# node24-power.net
KiCad netlist of a schematic drawn in Altium Designer
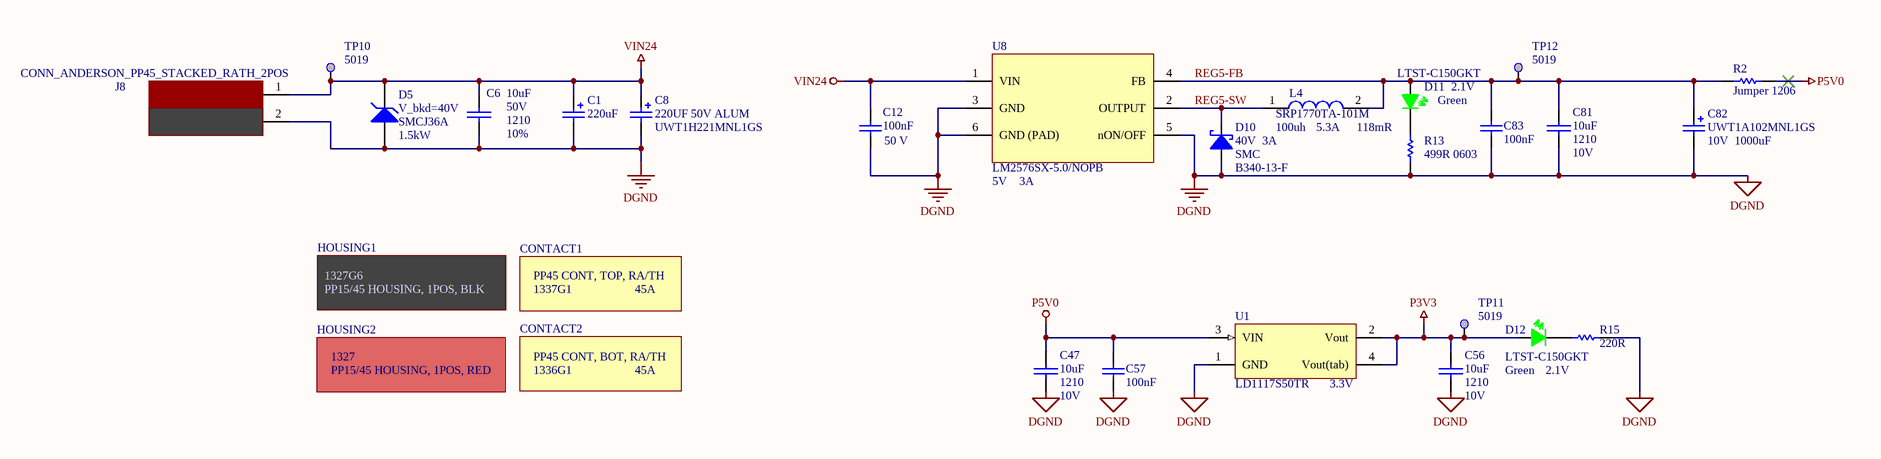
[diagram p0: node24-power.SchDoc]

(export (version "E")
  (design (tool "Eeschema 10.0.6"))
  (components
    (comp (ref "C1")
      (value "220UF ALUM 10MM")
      (footprint "CAPAE_D10_BH10MM3")
      (description "CAP ALUM 220UF 20% 50V SMD")
      (fields
        (field (name "MANUFACTURER") "Nichicon")
        (field (name "CAPACITANCE") "220uF")
        (field (name "TOLERANCE") "20%")
      )
      (libsource (lib "node") (part "CAP_ALUM_220UF_10MM_UWT1H221MNL1GS"))
    )
    (comp (ref "C6")
      (value "CAP_CER_10UF_50V_1210_GRJ32ER71H106KE11L")
      (footprint "CAP1210")
      (description "10µF 50V Ceramic Capacitor X7R 1210 (3225 Metric) 0.126\" L x 0.098\" W (3.20mm x 2.50mm)")
      (fields
        (field (name "MANUFACTURER") "Murata")
        (field (name "MANUFACTURER PART NUMBER") "GRJ32ER71H106KE11L")
        (field (name "TOLERANCE") "10%")
        (field (name "VOLTAGE RATING") "50V")
        (field (name "CAPACITANCE") "10uF")
        (field (name "CASE/PACKAGE") "1210")
      )
      (libsource (lib "node") (part "CAP_CER_10UF_50V_1210_GRJ32ER71H106KE11L"))
    )
    (comp (ref "C8")
      (value "220UF 50V ALUM")
      (footprint "CAPAE_D10_BH10MM3")
      (description "CAP ALUM 220UF 20% 50V SMD")
      (fields
        (field (name "MANUFACTURER") "Nichicon")
        (field (name "TOLERANCE") "20%")
        (field (name "MANUFACTURER PART NUMBER") "UWT1H221MNL1GS")
      )
      (libsource (lib "node") (part "CAP_ALUM_220UF_10MM_UWT1H221MNL1GS"))
    )
    (comp (ref "C12")
      (value "100nF")
      (footprint "CAPC0603(1608)100_L")
      (description "CAP 100nF 50V ±20% 0603 (1608 Metric) Thickness 1mm SMD")
      (fields (field (name "TOLERANCE") "Â±20%") (field (name "RATED VOLTAGE") "50 V"))
      (libsource (lib "Altium Content Vault") (part "CAP"))
    )
    (comp (ref "C47")
      (value "CAP_CER_10UF_1210_CL32B106KPINNNE")
      (footprint "1210C")
      (description "Cap Ceramic 10uF 10V X7R 10% SMD 1210 125C Embossed T/R")
      (fields
        (field (name "MANUFACTURER") "Samsung")
        (field (name "MANUFACTURER PART NUMBER") "CL32B106KPINNNE")
        (field (name "CAPACITANCE") "10uF")
        (field (name "CASE/PACKAGE") "1210")
        (field (name "VOLTAGE RATING") "10V")
      )
      (libsource (lib "node") (part "CAP_CER_10UF_1210_CL32B106KPINNNE"))
    )
    (comp (ref "C56")
      (value "CAP_CER_10UF_1210_CL32B106KPINNNE")
      (footprint "1210C")
      (description "Cap Ceramic 10uF 10V X7R 10% SMD 1210 125C Embossed T/R")
      (fields
        (field (name "MANUFACTURER") "Samsung")
        (field (name "MANUFACTURER PART NUMBER") "CL32B106KPINNNE")
        (field (name "CAPACITANCE") "10uF")
        (field (name "CASE/PACKAGE") "1210")
        (field (name "VOLTAGE RATING") "10V")
      )
      (libsource (lib "node") (part "CAP_CER_10UF_1210_CL32B106KPINNNE"))
    )
    (comp (ref "C57")
      (value "100nF")
      (footprint "CAPC0603(1608)100_L")
      (description "CAP 100nF 50V ±20% 0603 (1608 Metric) Thickness 1mm SMD")
      (fields (field (name "TOLERANCE") "Â±20%"))
      (libsource (lib "Altium Content Vault") (part "CAP"))
    )
    (comp (ref "C81")
      (value "CAP_CER_10UF_1210_CL32B106KPINNNE")
      (footprint "1210C")
      (description "Cap Ceramic 10uF 10V X7R 10% SMD 1210 125C Embossed T/R")
      (fields
        (field (name "MANUFACTURER") "Samsung")
        (field (name "MANUFACTURER PART NUMBER") "CL32B106KPINNNE")
        (field (name "CAPACITANCE") "10uF")
        (field (name "CASE/PACKAGE") "1210")
        (field (name "VOLTAGE RATING") "10V")
      )
      (libsource (lib "node") (part "CAP_CER_10UF_1210_CL32B106KPINNNE"))
    )
    (comp (ref "C82")
      (value "CAP_ALUM_10V_1000UF_10MM_UWT1A102MNL1GS")
      (footprint "CAPAE_D10_BH10MM3")
      (description "CAP ALUM 1000UF 20% 10V SMD")
      (fields
        (field (name "MANUFACTURER") "Nichicon")
        (field (name "TOLERANCE") "20%")
        (field (name "MANUFACTURER PART NUMBER") "UWT1A102MNL1GS")
        (field (name "VOLTAGE") "10V")
        (field (name "CAPACITANCE") "1000uF")
      )
      (libsource (lib "node") (part "CAP_ALUM_10V_1000UF_10MM_UWT1A102MNL1GS"))
    )
    (comp (ref "C83")
      (value "100nF")
      (footprint "CAPC0603(1608)100_L")
      (description "CAP 100nF 50V ±20% 0603 (1608 Metric) Thickness 1mm SMD")
      (fields (field (name "TOLERANCE") "Â±20%"))
      (libsource (lib "Altium Content Vault") (part "CAP"))
    )
    (comp (ref "CONTACT1")
      (value "CONN_ANDERSON_CONTACT_PP45_RATH_BOTTOM_1337G1")
      (description "Heavy Duty Power Connectors PCB45 HORIZ (TOP) RA LP CONT.")
      (fields
        (field (name "MANUFACTURER") "Anderson Power")
        (field (name "CURRENT RATING") "45A")
        (field (name "MANUFACTURER PART NUMBER") "1337G1")
        (field (name "PARAMETER 1") "PP45 CONT, TOP, RA/TH")
      )
      (libsource (lib "node") (part "CONN_ANDERSON_CONTACT_PP45_RATH_BOTTOM_1337G1"))
    )
    (comp (ref "CONTACT2")
      (value "CONN_ANDERSON_CONTACT_PP45_RATH_TOP_1336G1")
      (description "Heavy Duty Power Connectors PCB45 HORIZ. (BOT) RA LP CONT.")
      (fields
        (field (name "MANUFACTURER") "Anderson Power")
        (field (name "PARAMETER 1") "PP45 CONT, BOT, RA/TH")
        (field (name "CURRENT RATING") "45A")
        (field (name "MANUFACTURER PART NUMBER") "1336G1")
      )
      (libsource (lib "node") (part "CONN_ANDERSON_CONTACT_PP45_RATH_TOP_1336G1"))
    )
    (comp (ref "D5")
      (value "TVS_36V_1500W_SMC_SMCJ36A")
      (footprint "DIODE_SMC")
      (description "TVS DIODE 36VWM 58.1VC SMC")
      (fields
        (field (name "MANUFACTURER") "Littelfuse")
        (field (name "POWER DISSIPATION") "1.5kW")
        (field (name "MANUFACTURER PART NUMBER") "SMCJ36A")
        (field (name "BREAKDOWN VOLTAGE") "V_bkd=40V")
      )
      (libsource (lib "node") (part "TVS_36V_1500W_SMC_SMCJ36A"))
    )
    (comp (ref "D10")
      (value "DIODE_SCHOTTKY_40V_3A_SMC_DIO_B340-13-F")
      (footprint "DIODE_SMC")
      (description "DIODE SCHOTTKY 40V 3A SMC")
      (fields
        (field (name "MANUFACTURER") "Diodes")
        (field (name "VOLTAGE") "40V")
        (field (name "MANUFACTURER PART NUMBER") "B340-13-F")
        (field (name "CASE/PACKAGE") "SMC")
        (field (name "MAX REVERSE VOLTAGE (DC)") "40V")
        (field (name "CURRENT") "3A")
      )
      (libsource (lib "node") (part "DIODE_SCHOTTKY_40V_3A_SMC_DIO_B340-13-F"))
    )
    (comp (ref "D11")
      (value "LED_LITEON_GREEN_1206_LTST-C150GKT")
      (footprint "LED_1206")
      (description "LED GREEN CLEAR 1206 SMD")
      (fields
        (field (name "MANUFACTURER") "Vishay Lite-On")
        (field (name "FORWARD VOLTAGE") "2.1V")
        (field (name "ILLUMINATION COLOUR") "Green")
        (field (name "MANUFACTURER PART NUMBER") "LTST-C150GKT")
      )
      (libsource (lib "node") (part "LED_LITEON_GREEN_1206_LTST-C150GKT"))
    )
    (comp (ref "D12")
      (value "LED_LITEON_GREEN_1206_LTST-C150GKT")
      (footprint "LED_1206")
      (description "LED GREEN CLEAR 1206 SMD")
      (fields
        (field (name "MANUFACTURER") "Vishay Lite-On")
        (field (name "FORWARD VOLTAGE") "2.1V")
        (field (name "ILLUMINATION COLOUR") "Green")
        (field (name "MANUFACTURER PART NUMBER") "LTST-C150GKT")
      )
      (libsource (lib "node") (part "LED_LITEON_GREEN_1206_LTST-C150GKT"))
    )
    (comp (ref "HOUSING1")
      (value "CONN_ANDERSON_HOUSING_PP45/15_BLACK_1327G6")
      (description "Heavy Duty Power Connectors PP15/45 HOUSING ONLY BLACK")
      (fields
        (field (name "MANUFACTURER") "Anderson Power")
        (field (name "MANUFACTURER PART NUMBER") "1327G6")
        (field (name "PARAMETER 1") "PP15/45 HOUSING, 1POS, BLK")
      )
      (libsource (lib "node") (part "CONN_ANDERSON_HOUSING_PP45/15_BLACK_1327G6"))
    )
    (comp (ref "HOUSING2")
      (value "CONN_ANDERSON_HOUSING_PP45/15_RED_1327")
      (description "CONNECTOR HOUSING, 1POS, RED")
      (fields
        (field (name "MANUFACTURER") "Anderson Power")
        (field (name "MANUFACTURER PART NUMBER") "1327")
        (field (name "PARAMETER 1") "PP15/45 HOUSING, 1POS, RED")
      )
      (libsource (lib "node") (part "CONN_ANDERSON_HOUSING_PP45/15_RED_1327"))
    )
    (comp (ref "J8")
      (value "CONN_ANDERSON_PP45_STACKED_RATH_2POS")
      (footprint "CONN_ANDERSON_POWERPOLE_45_HOUSING_STACKED_RATH")
      (description "Powerpole PP15/45, Stacked 2pos")
      (fields (field (name "MANUFACTURER PART NUMBER") "See other parts for component data"))
      (libsource (lib "node") (part "CONN_ANDERSON_PP45_STACKED_RATH_2POS"))
    )
    (comp (ref "L4")
      (value "IND_100UH_5A3_SRP1770TA-101M")
      (footprint "IND_17MM_SMT")
      (description "Surface Mount Power Inductor, SRP1770TA Series, 100UH, 5.3 A, 12 A, Shielded, 0.118 ohm")
      (fields
        (field (name "MANUFACTURER") "Bourns")
        (field (name "TOLERANCE") "20%")
        (field (name "INDUCTANCE") "100uh")
        (field (name "DC RESISTANCE (DCR)") "118mR")
        (field (name "MANUFACTURER PART NUMBER") "SRP1770TA-101M")
        (field (name "CURRENT RATING") "5.3A")
      )
      (libsource (lib "node") (part "IND_100UH_5A3_SRP1770TA-101M"))
    )
    (comp (ref "R2")
      (value "Jumper 1206")
      (footprint "RESC1206(3216)_L")
      (description "Jumper 1206 (3216 Metric)")
      (fields (field (name "TOLERANCE") "None"))
      (libsource (lib "Altium Content Vault") (part "RES"))
    )
    (comp (ref "R13")
      (value "499R 0603")
      (footprint "RESC0603(1608)_L")
      (description "499R 0.1W 1% 0603 (1608 Metric)  SMD")
      (fields (field (name "POWER") "0.1 W") (field (name "TOLERANCE") "1 %"))
      (libsource (lib "Altium Content Vault") (part "RES"))
    )
    (comp (ref "R15")
      (value "220R")
      (footprint "RESC0603(1608)_L")
      (description "220R 0.1W 1% 0603 (1608 Metric)  SMD")
      (fields (field (name "TOLERANCE") "1 %") (field (name "POWER") "0.1 W"))
      (libsource (lib "Altium Content Vault") (part "RES"))
    )
    (comp (ref "TP10")
      (value "TEST_POINT_KEYSTONE_5019_SMT")
      (footprint "TEST_POINT_KEYSTONE_5019")
      (description "Circuit Board Hardware - PCB TEST POINT")
      (fields
        (field (name "MANUFACTURER") "Keystone Electronics")
        (field (name "MANUFACTURER PART NUMBER") "5019")
      )
      (libsource (lib "node") (part "TEST_POINT_KEYSTONE_5019_SMT"))
    )
    (comp (ref "TP11")
      (value "TEST_POINT_KEYSTONE_5019_SMT")
      (footprint "TEST_POINT_KEYSTONE_5019")
      (description "Circuit Board Hardware - PCB TEST POINT")
      (fields
        (field (name "MANUFACTURER") "Keystone Electronics")
        (field (name "MANUFACTURER PART NUMBER") "5019")
      )
      (libsource (lib "node") (part "TEST_POINT_KEYSTONE_5019_SMT"))
    )
    (comp (ref "TP12")
      (value "TEST_POINT_KEYSTONE_5019_SMT")
      (footprint "TEST_POINT_KEYSTONE_5019")
      (description "Circuit Board Hardware - PCB TEST POINT")
      (fields
        (field (name "MANUFACTURER") "Keystone Electronics")
        (field (name "MANUFACTURER PART NUMBER") "5019")
      )
      (libsource (lib "node") (part "TEST_POINT_KEYSTONE_5019_SMT"))
    )
    (comp (ref "U1")
      (value "LD1117S50TR")
      (footprint "SOT-223")
      (description "Fixed LDO Voltage Regulator, 5.3V to 15V, 1.1V Dropout, 3.3Vout, 950mAout, SOT-223-4")
      (fields
        (field (name "MANUFACTURER") "STMicroelectronics")
        (field (name "MANUFACTURER PART NUMBER") "LD1117S33CTR")
        (field (name "MAX OUTPUT VOLTAGE") "3.3V")
      )
      (libsource (lib "node") (part "LDO_ST_3V3_950mA_LD1117"))
    )
    (comp (ref "U8")
      (value "DCDC_TI_BUCK_REG_5V_3A_40VIN_D2PAK_LM2576SX-5.0/NOPB")
      (footprint "D2PAK_TO-263-6")
      (description "Conv DC-DC Single Non-Inv/Inv/Step Up/Step Down 4V to 40V 6-Pin(5+Tab) TO-263 T/R")
      (fields
        (field (name "MANUFACTURER") "TI National Semiconductor")
        (field (name "MANUFACTURER PART NUMBER") "LM2576SX-5.0/NOPB")
        (field (name "OUTPUT VOLTAGE") "5V")
        (field (name "MAX OUTPUT CURRENT") "3A")
      )
      (libsource (lib "node") (part "DCDC_TI_BUCK_REG_5V_3A_40VIN_D2PAK_LM2576SX-5.0/NOPB"))
    )
  )
  (nets
    (net (code "1") (name "/REG5-FB") (class "Default")
      (node (ref "C81") (pin "1") (pinfunction "1_1") (pintype "passive"))
      (node (ref "C82") (pin "1") (pinfunction "1_1") (pintype "passive"))
      (node (ref "C83") (pin "1") (pinfunction "1_1") (pintype "passive"))
      (node (ref "D11") (pin "1") (pinfunction "1_1") (pintype "passive"))
      (node (ref "L4") (pin "2") (pinfunction "2_2") (pintype "passive"))
      (node (ref "R2") (pin "1") (pinfunction "1_1") (pintype "passive"))
      (node (ref "TP12") (pin "1") (pinfunction "1_1") (pintype "passive"))
      (node (ref "U8") (pin "4") (pinfunction "FB_4") (pintype "passive"))
    )
    (net (code "2") (name "/REG5-SW") (class "Default")
      (node (ref "D10") (pin "2") (pinfunction "K_2") (pintype "passive"))
      (node (ref "L4") (pin "1") (pinfunction "1_1") (pintype "passive"))
      (node (ref "U8") (pin "2") (pinfunction "OUTPUT_2") (pintype "passive"))
    )
    (net (code "3") (name "DGND") (class "Default")
      (node (ref "C1") (pin "2") (pinfunction "2_2") (pintype "passive"))
      (node (ref "C12") (pin "2") (pinfunction "2_2") (pintype "passive"))
      (node (ref "C47") (pin "2") (pinfunction "2_2") (pintype "passive"))
      (node (ref "C56") (pin "2") (pinfunction "2_2") (pintype "passive"))
      (node (ref "C57") (pin "2") (pinfunction "2_2") (pintype "passive"))
      (node (ref "C6") (pin "2") (pinfunction "2_2") (pintype "passive"))
      (node (ref "C8") (pin "2") (pinfunction "2_2") (pintype "passive"))
      (node (ref "C81") (pin "2") (pinfunction "2_2") (pintype "passive"))
      (node (ref "C82") (pin "2") (pinfunction "2_2") (pintype "passive"))
      (node (ref "C83") (pin "2") (pinfunction "2_2") (pintype "passive"))
      (node (ref "D10") (pin "1") (pinfunction "A_1") (pintype "passive"))
      (node (ref "D5") (pin "1") (pinfunction "K_1") (pintype "passive"))
      (node (ref "J8") (pin "2") (pinfunction "2_2") (pintype "passive"))
      (node (ref "R13") (pin "2") (pinfunction "2_2") (pintype "passive"))
      (node (ref "R15") (pin "1") (pinfunction "1_1") (pintype "passive"))
      (node (ref "U1") (pin "1") (pinfunction "GND_1") (pintype "passive"))
      (node (ref "U8") (pin "3") (pinfunction "GND_3") (pintype "passive"))
      (node (ref "U8") (pin "5") (pinfunction "nON/OFF_5") (pintype "passive"))
      (node (ref "U8") (pin "6") (pinfunction "GND_(PAD)_6") (pintype "passive"))
    )
    (net (code "4") (name "Net-(D11-Pad2)") (class "Default")
      (node (ref "D11") (pin "2") (pinfunction "2_2") (pintype "passive"))
      (node (ref "R13") (pin "1") (pinfunction "1_1") (pintype "passive"))
    )
    (net (code "5") (name "Net-(D12-Pad2)") (class "Default")
      (node (ref "D12") (pin "2") (pinfunction "2_2") (pintype "passive"))
      (node (ref "R15") (pin "2") (pinfunction "2_2") (pintype "passive"))
    )
    (net (code "6") (name "P3V3") (class "Default")
      (node (ref "C56") (pin "1") (pinfunction "1_1") (pintype "passive"))
      (node (ref "D12") (pin "1") (pinfunction "1_1") (pintype "passive"))
      (node (ref "TP11") (pin "1") (pinfunction "1_1") (pintype "passive"))
      (node (ref "U1") (pin "2") (pinfunction "Vout_2") (pintype "power_in"))
      (node (ref "U1") (pin "4") (pinfunction "Vout(tab)_4") (pintype "power_in"))
    )
    (net (code "7") (name "P5V0") (class "Default")
      (node (ref "C47") (pin "1") (pinfunction "1_1") (pintype "passive"))
      (node (ref "C57") (pin "1") (pinfunction "1_1") (pintype "passive"))
      (node (ref "R2") (pin "2") (pinfunction "2_2") (pintype "passive"))
      (node (ref "U1") (pin "3") (pinfunction "VIN_3") (pintype "input"))
    )
    (net (code "8") (name "VIN24") (class "Default")
      (node (ref "C1") (pin "1") (pinfunction "1_1") (pintype "passive"))
      (node (ref "C12") (pin "1") (pinfunction "1_1") (pintype "passive"))
      (node (ref "C6") (pin "1") (pinfunction "1_1") (pintype "passive"))
      (node (ref "C8") (pin "1") (pinfunction "1_1") (pintype "passive"))
      (node (ref "D5") (pin "2") (pinfunction "A_2") (pintype "passive"))
      (node (ref "J8") (pin "1") (pinfunction "1_1") (pintype "passive"))
      (node (ref "TP10") (pin "1") (pinfunction "1_1") (pintype "passive"))
      (node (ref "U8") (pin "1") (pinfunction "VIN_1") (pintype "passive"))
    )
  )
)
